# 05_POWER.net
KiCad netlist of a schematic drawn in Altium Designer
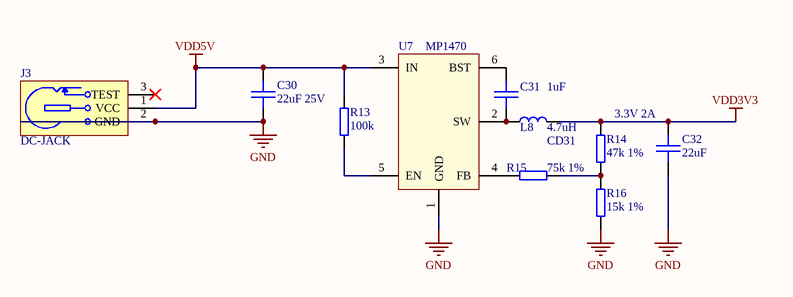
[diagram p0: 05_POWER.SchDoc]

(export (version "E")
  (design (tool "Eeschema 10.0.6"))
  (components
    (comp (ref "C30")
      (value "22uF 25V")
      (footprint "SMT_C_0805")
      (description "Surface mount capacitor 0805")
      (libsource (lib "Vowstar_Basic_Device") (part "SMT_C_0805"))
    )
    (comp (ref "C31")
      (value "1uF")
      (footprint "SMT_C_0402")
      (description "Surface mount capacitor 0402")
      (libsource (lib "Vowstar_Basic_Device") (part "SMT_C_0402"))
    )
    (comp (ref "C32")
      (value "22uF")
      (footprint "SMT_C_0805")
      (description "Surface mount capacitor 0805")
      (libsource (lib "Vowstar_Basic_Device") (part "SMT_C_0805"))
    )
    (comp (ref "J3")
      (value "DC-JACK")
      (footprint "DC-JACK-6.2mm")
      (description "电源插孔")
      (libsource (lib "Vowstar_Connector") (part "DC-JACK"))
    )
    (comp (ref "L8")
      (value "4.7uH")
      (footprint "SMT_L_3.3mm")
      (description "LPO3310 SMT Power Inductor, 3.3x3.3x1mm")
      (libsource (lib "Vowstar_Basic_Device") (part "SMT_L_3.3mm"))
    )
    (comp (ref "R13")
      (value "100k")
      (footprint "SMT_R_0402")
      (description "Surface mount resistor 0402")
      (libsource (lib "Vowstar_Basic_Device") (part "SMT_R_0402"))
    )
    (comp (ref "R14")
      (value "47k 1%")
      (footprint "SMT_R_0402")
      (description "Surface mount resistor 0402")
      (libsource (lib "Vowstar_Basic_Device") (part "SMT_R_0402"))
    )
    (comp (ref "R15")
      (value "75k 1%")
      (footprint "SMT_R_0402")
      (description "Surface mount resistor 0402")
      (libsource (lib "Vowstar_Basic_Device") (part "SMT_R_0402"))
    )
    (comp (ref "R16")
      (value "15k 1%")
      (footprint "SMT_R_0402")
      (description "Surface mount resistor 0402")
      (libsource (lib "Vowstar_Basic_Device") (part "SMT_R_0402"))
    )
    (comp (ref "U7")
      (value "MP1470")
      (footprint "SOT23-6")
      (description "High-Efficiency, 2A, 16V, 500kHz  Synchronous, Step-Down Converter")
      (libsource (lib "Vowstar_IC_General") (part "MP1470"))
    )
  )
  (nets
    (net (code "1") (name "GND") (class "Default")
      (node (ref "C30") (pin "2") (pinfunction "2_2") (pintype "passive"))
      (node (ref "C32") (pin "2") (pinfunction "2_2") (pintype "passive"))
      (node (ref "J3") (pin "2") (pinfunction "GND_2") (pintype "passive"))
      (node (ref "R16") (pin "2") (pinfunction "2_2") (pintype "passive"))
      (node (ref "U7") (pin "1") (pinfunction "GND_1") (pintype "passive"))
    )
    (net (code "2") (name "Net-(R14-Pad2)") (class "Default")
      (node (ref "R14") (pin "2") (pinfunction "2_2") (pintype "passive"))
      (node (ref "R15") (pin "1") (pinfunction "1_1") (pintype "passive"))
      (node (ref "R16") (pin "1") (pinfunction "1_1") (pintype "passive"))
    )
    (net (code "3") (name "Net-(U7-BST)") (class "Default")
      (node (ref "C31") (pin "1") (pinfunction "1_1") (pintype "passive"))
      (node (ref "U7") (pin "6") (pinfunction "BST_6") (pintype "passive"))
    )
    (net (code "4") (name "Net-(U7-EN)") (class "Default")
      (node (ref "R13") (pin "1") (pinfunction "1_1") (pintype "passive"))
      (node (ref "U7") (pin "5") (pinfunction "EN_5") (pintype "passive"))
    )
    (net (code "5") (name "Net-(U7-FB)") (class "Default")
      (node (ref "R15") (pin "2") (pinfunction "2_2") (pintype "passive"))
      (node (ref "U7") (pin "4") (pinfunction "FB_4") (pintype "passive"))
    )
    (net (code "6") (name "Net-(U7-SW)") (class "Default")
      (node (ref "C31") (pin "2") (pinfunction "2_2") (pintype "passive"))
      (node (ref "L8") (pin "2") (pinfunction "2_2") (pintype "passive"))
      (node (ref "U7") (pin "2") (pinfunction "SW_2") (pintype "passive"))
    )
    (net (code "7") (name "VDD3V3") (class "Default")
      (node (ref "C32") (pin "1") (pinfunction "1_1") (pintype "passive"))
      (node (ref "L8") (pin "1") (pinfunction "1_1") (pintype "passive"))
      (node (ref "R14") (pin "1") (pinfunction "1_1") (pintype "passive"))
    )
    (net (code "8") (name "VDD5V") (class "Default")
      (node (ref "C30") (pin "1") (pinfunction "1_1") (pintype "passive"))
      (node (ref "J3") (pin "1") (pinfunction "VCC_1") (pintype "passive"))
      (node (ref "R13") (pin "2") (pinfunction "2_2") (pintype "passive"))
      (node (ref "U7") (pin "3") (pinfunction "IN_3") (pintype "passive"))
    )
    (net (code "9") (name "unconnected-(J3-TEST-Pad3)") (class "Default")
      (node (ref "J3") (pin "3") (pinfunction "TEST_3") (pintype "passive+no_connect"))
    )
  )
)
